# axiom_beta_plugin_module_1xHDMI_v0_6_r1_.net
KiCad netlist of a schematic drawn in EAGLE
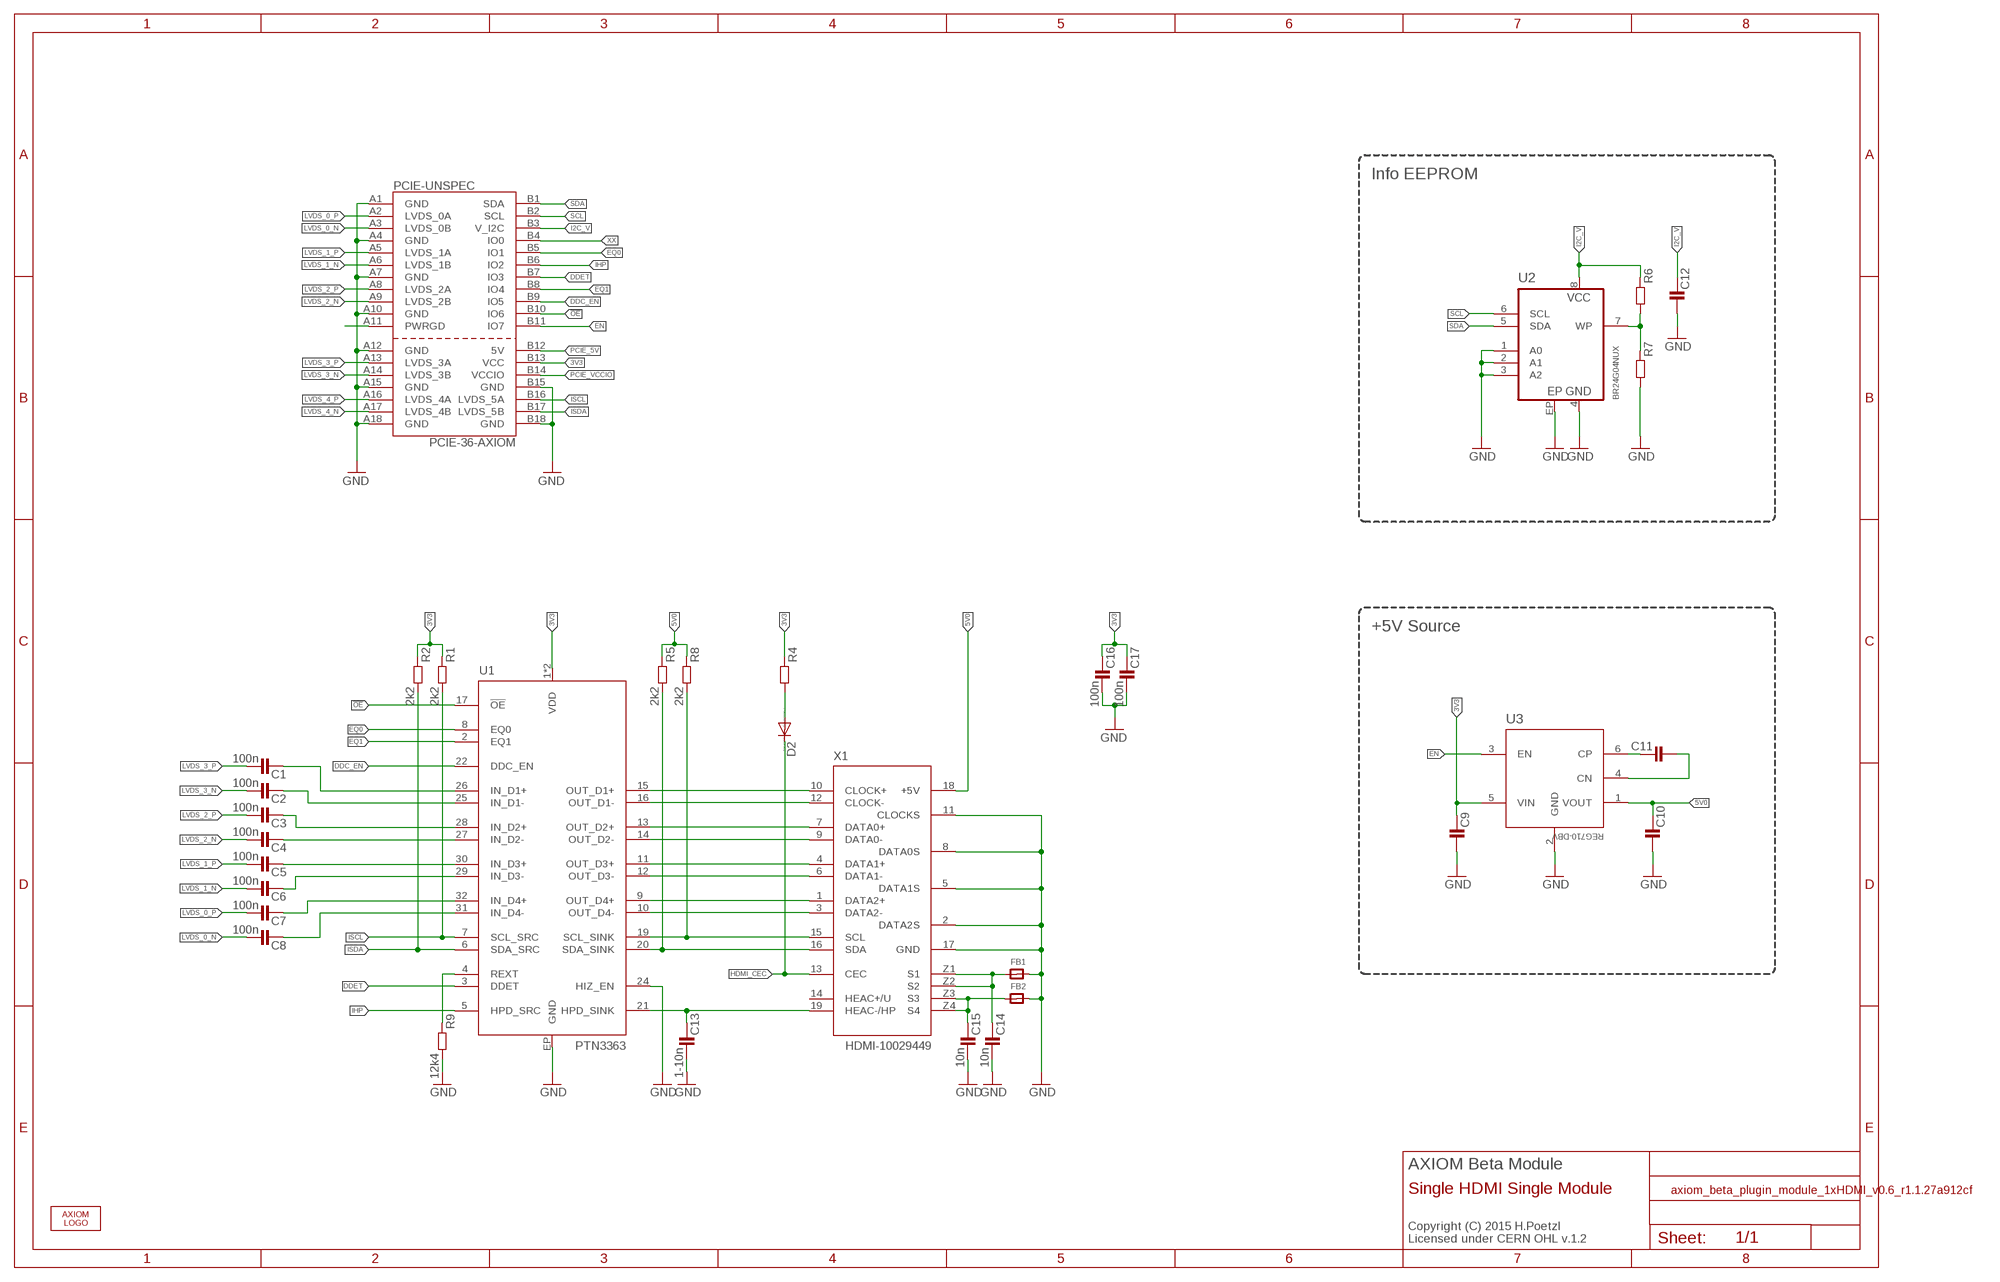
[diagram p0: schematic, sheet 1]

(export (version "E")
  (design (tool "Eeschema 10.0.6"))
  (components
    (comp (ref "C1")
      (value "100n")
      (footprint "eagle-import:0402-C")
      (libsource (lib "eagle-import") (part "C0402-C"))
    )
    (comp (ref "C2")
      (value "100n")
      (footprint "eagle-import:0402-C")
      (libsource (lib "eagle-import") (part "C0402-C"))
    )
    (comp (ref "C3")
      (value "100n")
      (footprint "eagle-import:0402-C")
      (libsource (lib "eagle-import") (part "C0402-C"))
    )
    (comp (ref "C4")
      (value "100n")
      (footprint "eagle-import:0402-C")
      (libsource (lib "eagle-import") (part "C0402-C"))
    )
    (comp (ref "C5")
      (value "100n")
      (footprint "eagle-import:0402-C")
      (libsource (lib "eagle-import") (part "C0402-C"))
    )
    (comp (ref "C6")
      (value "100n")
      (footprint "eagle-import:0402-C")
      (libsource (lib "eagle-import") (part "C0402-C"))
    )
    (comp (ref "C7")
      (value "100n")
      (footprint "eagle-import:0402-C")
      (libsource (lib "eagle-import") (part "C0402-C"))
    )
    (comp (ref "C8")
      (value "100n")
      (footprint "eagle-import:0402-C")
      (libsource (lib "eagle-import") (part "C0402-C"))
    )
    (comp (ref "C9")
      (value "C0603-B")
      (footprint "eagle-import:0603-B")
      (libsource (lib "eagle-import") (part "C0603-B"))
    )
    (comp (ref "C10")
      (value "C0603-B")
      (footprint "eagle-import:0603-B")
      (libsource (lib "eagle-import") (part "C0603-B"))
    )
    (comp (ref "C11")
      (value "C0603-B")
      (footprint "eagle-import:0603-B")
      (libsource (lib "eagle-import") (part "C0603-B"))
    )
    (comp (ref "C12")
      (value "C0402-B")
      (footprint "eagle-import:0402-B")
      (libsource (lib "eagle-import") (part "C0402-B"))
    )
    (comp (ref "C13")
      (value "1-10n")
      (footprint "eagle-import:0402-B")
      (libsource (lib "eagle-import") (part "C0402-B"))
    )
    (comp (ref "C14")
      (value "10n")
      (footprint "eagle-import:0402-B")
      (libsource (lib "eagle-import") (part "C0402-B"))
    )
    (comp (ref "C15")
      (value "10n")
      (footprint "eagle-import:0402-B")
      (libsource (lib "eagle-import") (part "C0402-B"))
    )
    (comp (ref "C16")
      (value "100n")
      (footprint "eagle-import:0402-B")
      (libsource (lib "eagle-import") (part "C0402-B"))
    )
    (comp (ref "C17")
      (value "100n")
      (footprint "eagle-import:0402-B")
      (libsource (lib "eagle-import") (part "C0402-B"))
    )
    (comp (ref "D2")
      (value "DIODE-SOD523")
      (footprint "eagle-import:SOD523")
      (libsource (lib "eagle-import") (part "DIODE-SOD523"))
    )
    (comp (ref "FB1")
      (value "FERRITE_0603MP")
      (footprint "eagle-import:_0603MP")
      (libsource (lib "eagle-import") (part "FERRITE_0603MP"))
    )
    (comp (ref "FB2")
      (value "FERRITE_0603MP")
      (footprint "eagle-import:_0603MP")
      (libsource (lib "eagle-import") (part "FERRITE_0603MP"))
    )
    (comp (ref "PCIE-UNSPEC")
      (value "PCIE-36-AXIOM")
      (footprint "eagle-import:PCIE-36-AXIOM")
      (libsource (lib "eagle-import") (part "PCIE-36-AXIOM"))
    )
    (comp (ref "R1")
      (value "2k2")
      (footprint "eagle-import:0402-B")
      (libsource (lib "eagle-import") (part "R0402-B"))
    )
    (comp (ref "R2")
      (value "2k2")
      (footprint "eagle-import:0402-B")
      (libsource (lib "eagle-import") (part "R0402-B"))
    )
    (comp (ref "R4")
      (value "R0402-B")
      (footprint "eagle-import:0402-B")
      (libsource (lib "eagle-import") (part "R0402-B"))
    )
    (comp (ref "R5")
      (value "2k2")
      (footprint "eagle-import:0402-B")
      (libsource (lib "eagle-import") (part "R0402-B"))
    )
    (comp (ref "R6")
      (value "R0402-B")
      (footprint "eagle-import:0402-B")
      (libsource (lib "eagle-import") (part "R0402-B"))
    )
    (comp (ref "R7")
      (value "R0402-B")
      (footprint "eagle-import:0402-B")
      (libsource (lib "eagle-import") (part "R0402-B"))
    )
    (comp (ref "R8")
      (value "2k2")
      (footprint "eagle-import:0402-B")
      (libsource (lib "eagle-import") (part "R0402-B"))
    )
    (comp (ref "R9")
      (value "12k4")
      (footprint "eagle-import:0402-B")
      (libsource (lib "eagle-import") (part "R0402-B"))
    )
    (comp (ref "U$1")
      (value "AXIOM_LOGO459X70")
      (footprint "eagle-import:AXIOM_LOGO_459X70")
      (libsource (lib "eagle-import") (part "AXIOM_LOGO459X70"))
    )
    (comp (ref "U1")
      (value "PTN3363")
      (footprint "eagle-import:HVQFN32")
      (libsource (lib "eagle-import") (part "PTN3363"))
    )
    (comp (ref "U2")
      (value "BR24G04NUX")
      (footprint "eagle-import:DFN200X300X100-9N")
      (libsource (lib "eagle-import") (part "BR24G04NUX"))
    )
    (comp (ref "U3")
      (value "REG710-DBV")
      (footprint "eagle-import:DBV")
      (libsource (lib "eagle-import") (part "REG710-DBV"))
    )
    (comp (ref "X1")
      (value "HDMI-10029449")
      (footprint "eagle-import:10029449-X01XLF")
      (libsource (lib "eagle-import") (part "HDMI-10029449"))
    )
  )
  (nets
    (net (code "1") (name "/~{OE}") (class "Default")
      (node (ref "PCIE-UNSPEC") (pin "B10") (pinfunction "IO6_B10") (pintype "passive"))
      (node (ref "U1") (pin "17") (pinfunction "~{OE}_17") (pintype "bidirectional"))
    )
    (net (code "2") (name "3V3") (class "Default")
      (node (ref "C16") (pin "1") (pinfunction "1_1") (pintype "passive"))
      (node (ref "C17") (pin "1") (pinfunction "1_1") (pintype "passive"))
      (node (ref "C9") (pin "1") (pinfunction "1_1") (pintype "passive"))
      (node (ref "PCIE-UNSPEC") (pin "B13") (pinfunction "VCC_B13") (pintype "passive"))
      (node (ref "R1") (pin "1") (pinfunction "1_1") (pintype "passive"))
      (node (ref "R2") (pin "1") (pinfunction "1_1") (pintype "passive"))
      (node (ref "R4") (pin "1") (pinfunction "1_1") (pintype "passive"))
      (node (ref "U1") (pin "1") (pinfunction "VDD_1") (pintype "power_in"))
      (node (ref "U1") (pin "18") (pinfunction "VDD_18") (pintype "power_in"))
      (node (ref "U3") (pin "5") (pinfunction "VIN_5") (pintype "power_in"))
    )
    (net (code "3") (name "5V0") (class "Default")
      (node (ref "C10") (pin "1") (pinfunction "1_1") (pintype "passive"))
      (node (ref "R5") (pin "1") (pinfunction "1_1") (pintype "passive"))
      (node (ref "R8") (pin "1") (pinfunction "1_1") (pintype "passive"))
      (node (ref "U3") (pin "1") (pinfunction "VOUT_1") (pintype "output"))
      (node (ref "X1") (pin "18") (pinfunction "+5V_18") (pintype "power_in"))
    )
    (net (code "4") (name "DDC_EN") (class "Default")
      (node (ref "PCIE-UNSPEC") (pin "B9") (pinfunction "IO5_B9") (pintype "passive"))
      (node (ref "U1") (pin "22") (pinfunction "DDC_EN_22") (pintype "bidirectional"))
    )
    (net (code "5") (name "DDET") (class "Default")
      (node (ref "PCIE-UNSPEC") (pin "B7") (pinfunction "IO3_B7") (pintype "passive"))
      (node (ref "U1") (pin "3") (pinfunction "DDET_3") (pintype "bidirectional"))
    )
    (net (code "6") (name "EN") (class "Default")
      (node (ref "PCIE-UNSPEC") (pin "B11") (pinfunction "IO7_B11") (pintype "passive"))
      (node (ref "U3") (pin "3") (pinfunction "EN_3") (pintype "input"))
    )
    (net (code "7") (name "EQ0") (class "Default")
      (node (ref "PCIE-UNSPEC") (pin "B5") (pinfunction "IO1_B5") (pintype "passive"))
      (node (ref "U1") (pin "8") (pinfunction "EQ0_8") (pintype "bidirectional"))
    )
    (net (code "8") (name "EQ1") (class "Default")
      (node (ref "PCIE-UNSPEC") (pin "B8") (pinfunction "IO4_B8") (pintype "passive"))
      (node (ref "U1") (pin "2") (pinfunction "EQ1_2") (pintype "bidirectional"))
    )
    (net (code "9") (name "GND") (class "Default")
      (node (ref "C10") (pin "2") (pinfunction "2_2") (pintype "passive"))
      (node (ref "C12") (pin "2") (pinfunction "2_2") (pintype "passive"))
      (node (ref "C13") (pin "2") (pinfunction "2_2") (pintype "passive"))
      (node (ref "C14") (pin "2") (pinfunction "2_2") (pintype "passive"))
      (node (ref "C15") (pin "2") (pinfunction "2_2") (pintype "passive"))
      (node (ref "C16") (pin "2") (pinfunction "2_2") (pintype "passive"))
      (node (ref "C17") (pin "2") (pinfunction "2_2") (pintype "passive"))
      (node (ref "C9") (pin "2") (pinfunction "2_2") (pintype "passive"))
      (node (ref "FB1") (pin "2") (pinfunction "P$2_2") (pintype "passive"))
      (node (ref "FB2") (pin "2") (pinfunction "P$2_2") (pintype "passive"))
      (node (ref "PCIE-UNSPEC") (pin "A1") (pinfunction "GND_A1") (pintype "passive"))
      (node (ref "PCIE-UNSPEC") (pin "A10") (pinfunction "GND_A10") (pintype "passive"))
      (node (ref "PCIE-UNSPEC") (pin "A12") (pinfunction "GND_A12") (pintype "passive"))
      (node (ref "PCIE-UNSPEC") (pin "A15") (pinfunction "GND_A15") (pintype "passive"))
      (node (ref "PCIE-UNSPEC") (pin "A18") (pinfunction "GND_A18") (pintype "passive"))
      (node (ref "PCIE-UNSPEC") (pin "A4") (pinfunction "GND_A4") (pintype "passive"))
      (node (ref "PCIE-UNSPEC") (pin "A7") (pinfunction "GND_A7") (pintype "passive"))
      (node (ref "PCIE-UNSPEC") (pin "B15") (pinfunction "GND_B15") (pintype "passive"))
      (node (ref "PCIE-UNSPEC") (pin "B18") (pinfunction "GND_B18") (pintype "passive"))
      (node (ref "R7") (pin "2") (pinfunction "2_2") (pintype "passive"))
      (node (ref "R9") (pin "2") (pinfunction "2_2") (pintype "passive"))
      (node (ref "U1") (pin "24") (pinfunction "HIZ_EN_24") (pintype "bidirectional"))
      (node (ref "U1") (pin "EP") (pinfunction "GND_EP") (pintype "bidirectional"))
      (node (ref "U2") (pin "1") (pinfunction "A0_1") (pintype "input"))
      (node (ref "U2") (pin "2") (pinfunction "A1_2") (pintype "input"))
      (node (ref "U2") (pin "3") (pinfunction "A2_3") (pintype "input"))
      (node (ref "U2") (pin "4") (pinfunction "GND_4") (pintype "passive"))
      (node (ref "U2") (pin "EP") (pinfunction "EP_EP") (pintype "passive"))
      (node (ref "U3") (pin "2") (pinfunction "GND_2") (pintype "passive"))
      (node (ref "X1") (pin "11") (pinfunction "CLOCKS_11") (pintype "power_in"))
      (node (ref "X1") (pin "17") (pinfunction "GND_17") (pintype "bidirectional"))
      (node (ref "X1") (pin "2") (pinfunction "DATA2S_2") (pintype "power_in"))
      (node (ref "X1") (pin "5") (pinfunction "DATA1S_5") (pintype "power_in"))
      (node (ref "X1") (pin "8") (pinfunction "DATA0S_8") (pintype "power_in"))
    )
    (net (code "10") (name "HDMI_CEC") (class "Default")
      (node (ref "D2") (pin "C") (pinfunction "C_C") (pintype "passive"))
      (node (ref "X1") (pin "13") (pinfunction "CEC_13") (pintype "bidirectional"))
    )
    (net (code "11") (name "I2C_V") (class "Default")
      (node (ref "C12") (pin "1") (pinfunction "1_1") (pintype "passive"))
      (node (ref "PCIE-UNSPEC") (pin "B3") (pinfunction "V_I2C_B3") (pintype "passive"))
      (node (ref "R6") (pin "1") (pinfunction "1_1") (pintype "passive"))
      (node (ref "U2") (pin "8") (pinfunction "VCC_8") (pintype "power_in"))
    )
    (net (code "12") (name "IHP") (class "Default")
      (node (ref "PCIE-UNSPEC") (pin "B6") (pinfunction "IO2_B6") (pintype "passive"))
      (node (ref "U1") (pin "5") (pinfunction "HPD_SRC_5") (pintype "bidirectional"))
    )
    (net (code "13") (name "ISCL") (class "Default")
      (node (ref "PCIE-UNSPEC") (pin "B16") (pinfunction "LVDS_5A_B16") (pintype "passive"))
      (node (ref "R1") (pin "2") (pinfunction "2_2") (pintype "passive"))
      (node (ref "U1") (pin "7") (pinfunction "SCL_SRC_7") (pintype "bidirectional"))
    )
    (net (code "14") (name "ISDA") (class "Default")
      (node (ref "PCIE-UNSPEC") (pin "B17") (pinfunction "LVDS_5B_B17") (pintype "passive"))
      (node (ref "R2") (pin "2") (pinfunction "2_2") (pintype "passive"))
      (node (ref "U1") (pin "6") (pinfunction "SDA_SRC_6") (pintype "bidirectional"))
    )
    (net (code "15") (name "LVDS_0_N") (class "Default")
      (node (ref "C8") (pin "2") (pinfunction "2_2") (pintype "passive"))
      (node (ref "PCIE-UNSPEC") (pin "A3") (pinfunction "LVDS_0B_A3") (pintype "passive"))
    )
    (net (code "16") (name "LVDS_0_P") (class "Default")
      (node (ref "C7") (pin "2") (pinfunction "2_2") (pintype "passive"))
      (node (ref "PCIE-UNSPEC") (pin "A2") (pinfunction "LVDS_0A_A2") (pintype "passive"))
    )
    (net (code "17") (name "LVDS_1_N") (class "Default")
      (node (ref "C6") (pin "2") (pinfunction "2_2") (pintype "passive"))
      (node (ref "PCIE-UNSPEC") (pin "A6") (pinfunction "LVDS_1B_A6") (pintype "passive"))
    )
    (net (code "18") (name "LVDS_1_P") (class "Default")
      (node (ref "C5") (pin "2") (pinfunction "2_2") (pintype "passive"))
      (node (ref "PCIE-UNSPEC") (pin "A5") (pinfunction "LVDS_1A_A5") (pintype "passive"))
    )
    (net (code "19") (name "LVDS_2_N") (class "Default")
      (node (ref "C4") (pin "2") (pinfunction "2_2") (pintype "passive"))
      (node (ref "PCIE-UNSPEC") (pin "A9") (pinfunction "LVDS_2B_A9") (pintype "passive"))
    )
    (net (code "20") (name "LVDS_2_P") (class "Default")
      (node (ref "C3") (pin "2") (pinfunction "2_2") (pintype "passive"))
      (node (ref "PCIE-UNSPEC") (pin "A8") (pinfunction "LVDS_2A_A8") (pintype "passive"))
    )
    (net (code "21") (name "LVDS_3_N") (class "Default")
      (node (ref "C2") (pin "2") (pinfunction "2_2") (pintype "passive"))
      (node (ref "PCIE-UNSPEC") (pin "A14") (pinfunction "LVDS_3B_A14") (pintype "passive"))
    )
    (net (code "22") (name "LVDS_3_P") (class "Default")
      (node (ref "C1") (pin "2") (pinfunction "2_2") (pintype "passive"))
      (node (ref "PCIE-UNSPEC") (pin "A13") (pinfunction "LVDS_3A_A13") (pintype "passive"))
    )
    (net (code "23") (name "LVDS_4_N") (class "Default")
      (node (ref "PCIE-UNSPEC") (pin "A17") (pinfunction "LVDS_4B_A17") (pintype "passive"))
    )
    (net (code "24") (name "LVDS_4_P") (class "Default")
      (node (ref "PCIE-UNSPEC") (pin "A16") (pinfunction "LVDS_4A_A16") (pintype "passive"))
    )
    (net (code "25") (name "Net-(D2-PadA)") (class "Default")
      (node (ref "D2") (pin "A") (pinfunction "A_A") (pintype "passive"))
      (node (ref "R4") (pin "2") (pinfunction "2_2") (pintype "passive"))
    )
    (net (code "26") (name "Net-(FB1-P$1)") (class "Default")
      (node (ref "C14") (pin "1") (pinfunction "1_1") (pintype "passive"))
      (node (ref "FB1") (pin "1") (pinfunction "P$1_1") (pintype "passive"))
      (node (ref "X1") (pin "Z1") (pinfunction "S1_Z1") (pintype "power_in"))
      (node (ref "X1") (pin "Z2") (pinfunction "S2_Z2") (pintype "power_in"))
    )
    (net (code "27") (name "Net-(FB2-P$1)") (class "Default")
      (node (ref "C15") (pin "1") (pinfunction "1_1") (pintype "passive"))
      (node (ref "FB2") (pin "1") (pinfunction "P$1_1") (pintype "passive"))
      (node (ref "X1") (pin "Z3") (pinfunction "S3_Z3") (pintype "power_in"))
      (node (ref "X1") (pin "Z4") (pinfunction "S4_Z4") (pintype "power_in"))
    )
    (net (code "28") (name "Net-(U1-HPD_SINK)") (class "Default")
      (node (ref "C13") (pin "1") (pinfunction "1_1") (pintype "passive"))
      (node (ref "U1") (pin "21") (pinfunction "HPD_SINK_21") (pintype "bidirectional"))
      (node (ref "X1") (pin "19") (pinfunction "HEAC-/HP_19") (pintype "bidirectional"))
    )
    (net (code "29") (name "Net-(U1-IN_D1+)") (class "Default")
      (node (ref "C1") (pin "1") (pinfunction "1_1") (pintype "passive"))
      (node (ref "U1") (pin "26") (pinfunction "IN_D1+_26") (pintype "bidirectional"))
    )
    (net (code "30") (name "Net-(U1-IN_D1-)") (class "Default")
      (node (ref "C2") (pin "1") (pinfunction "1_1") (pintype "passive"))
      (node (ref "U1") (pin "25") (pinfunction "IN_D1-_25") (pintype "bidirectional"))
    )
    (net (code "31") (name "Net-(U1-IN_D2+)") (class "Default")
      (node (ref "C3") (pin "1") (pinfunction "1_1") (pintype "passive"))
      (node (ref "U1") (pin "28") (pinfunction "IN_D2+_28") (pintype "bidirectional"))
    )
    (net (code "32") (name "Net-(U1-IN_D2-)") (class "Default")
      (node (ref "C4") (pin "1") (pinfunction "1_1") (pintype "passive"))
      (node (ref "U1") (pin "27") (pinfunction "IN_D2-_27") (pintype "bidirectional"))
    )
    (net (code "33") (name "Net-(U1-IN_D3+)") (class "Default")
      (node (ref "C5") (pin "1") (pinfunction "1_1") (pintype "passive"))
      (node (ref "U1") (pin "30") (pinfunction "IN_D3+_30") (pintype "bidirectional"))
    )
    (net (code "34") (name "Net-(U1-IN_D3-)") (class "Default")
      (node (ref "C6") (pin "1") (pinfunction "1_1") (pintype "passive"))
      (node (ref "U1") (pin "29") (pinfunction "IN_D3-_29") (pintype "bidirectional"))
    )
    (net (code "35") (name "Net-(U1-IN_D4+)") (class "Default")
      (node (ref "C7") (pin "1") (pinfunction "1_1") (pintype "passive"))
      (node (ref "U1") (pin "32") (pinfunction "IN_D4+_32") (pintype "bidirectional"))
    )
    (net (code "36") (name "Net-(U1-IN_D4-)") (class "Default")
      (node (ref "C8") (pin "1") (pinfunction "1_1") (pintype "passive"))
      (node (ref "U1") (pin "31") (pinfunction "IN_D4-_31") (pintype "bidirectional"))
    )
    (net (code "37") (name "Net-(U1-OUT_D1+)") (class "Default")
      (node (ref "U1") (pin "15") (pinfunction "OUT_D1+_15") (pintype "bidirectional"))
      (node (ref "X1") (pin "10") (pinfunction "CLOCK+_10") (pintype "bidirectional"))
    )
    (net (code "38") (name "Net-(U1-OUT_D1-)") (class "Default")
      (node (ref "U1") (pin "16") (pinfunction "OUT_D1-_16") (pintype "bidirectional"))
      (node (ref "X1") (pin "12") (pinfunction "CLOCK-_12") (pintype "bidirectional"))
    )
    (net (code "39") (name "Net-(U1-OUT_D2+)") (class "Default")
      (node (ref "U1") (pin "13") (pinfunction "OUT_D2+_13") (pintype "bidirectional"))
      (node (ref "X1") (pin "7") (pinfunction "DATA0+_7") (pintype "bidirectional"))
    )
    (net (code "40") (name "Net-(U1-OUT_D2-)") (class "Default")
      (node (ref "U1") (pin "14") (pinfunction "OUT_D2-_14") (pintype "bidirectional"))
      (node (ref "X1") (pin "9") (pinfunction "DATA0-_9") (pintype "bidirectional"))
    )
    (net (code "41") (name "Net-(U1-OUT_D3+)") (class "Default")
      (node (ref "U1") (pin "11") (pinfunction "OUT_D3+_11") (pintype "bidirectional"))
      (node (ref "X1") (pin "4") (pinfunction "DATA1+_4") (pintype "bidirectional"))
    )
    (net (code "42") (name "Net-(U1-OUT_D3-)") (class "Default")
      (node (ref "U1") (pin "12") (pinfunction "OUT_D3-_12") (pintype "bidirectional"))
      (node (ref "X1") (pin "6") (pinfunction "DATA1-_6") (pintype "bidirectional"))
    )
    (net (code "43") (name "Net-(U1-OUT_D4+)") (class "Default")
      (node (ref "U1") (pin "9") (pinfunction "OUT_D4+_9") (pintype "bidirectional"))
      (node (ref "X1") (pin "1") (pinfunction "DATA2+_1") (pintype "bidirectional"))
    )
    (net (code "44") (name "Net-(U1-OUT_D4-)") (class "Default")
      (node (ref "U1") (pin "10") (pinfunction "OUT_D4-_10") (pintype "bidirectional"))
      (node (ref "X1") (pin "3") (pinfunction "DATA2-_3") (pintype "bidirectional"))
    )
    (net (code "45") (name "Net-(U1-REXT)") (class "Default")
      (node (ref "R9") (pin "1") (pinfunction "1_1") (pintype "passive"))
      (node (ref "U1") (pin "4") (pinfunction "REXT_4") (pintype "bidirectional"))
    )
    (net (code "46") (name "Net-(U1-SCL_SINK)") (class "Default")
      (node (ref "R8") (pin "2") (pinfunction "2_2") (pintype "passive"))
      (node (ref "U1") (pin "19") (pinfunction "SCL_SINK_19") (pintype "bidirectional"))
      (node (ref "X1") (pin "15") (pinfunction "SCL_15") (pintype "bidirectional"))
    )
    (net (code "47") (name "Net-(U1-SDA_SINK)") (class "Default")
      (node (ref "R5") (pin "2") (pinfunction "2_2") (pintype "passive"))
      (node (ref "U1") (pin "20") (pinfunction "SDA_SINK_20") (pintype "bidirectional"))
      (node (ref "X1") (pin "16") (pinfunction "SDA_16") (pintype "bidirectional"))
    )
    (net (code "48") (name "Net-(U2-WP)") (class "Default")
      (node (ref "R6") (pin "2") (pinfunction "2_2") (pintype "passive"))
      (node (ref "R7") (pin "1") (pinfunction "1_1") (pintype "passive"))
      (node (ref "U2") (pin "7") (pinfunction "WP_7") (pintype "input"))
    )
    (net (code "49") (name "Net-(U3-CN)") (class "Default")
      (node (ref "C11") (pin "2") (pinfunction "2_2") (pintype "passive"))
      (node (ref "U3") (pin "4") (pinfunction "CN_4") (pintype "power_in"))
    )
    (net (code "50") (name "Net-(U3-CP)") (class "Default")
      (node (ref "C11") (pin "1") (pinfunction "1_1") (pintype "passive"))
      (node (ref "U3") (pin "6") (pinfunction "CP_6") (pintype "output"))
    )
    (net (code "51") (name "PCIE_5V") (class "Default")
      (node (ref "PCIE-UNSPEC") (pin "B12") (pinfunction "5V_B12") (pintype "passive"))
    )
    (net (code "52") (name "PCIE_VCCIO") (class "Default")
      (node (ref "PCIE-UNSPEC") (pin "B14") (pinfunction "VCCIO_B14") (pintype "passive"))
    )
    (net (code "53") (name "SCL") (class "Default")
      (node (ref "PCIE-UNSPEC") (pin "B2") (pinfunction "SCL_B2") (pintype "passive"))
      (node (ref "U2") (pin "6") (pinfunction "SCL_6") (pintype "input"))
    )
    (net (code "54") (name "SDA") (class "Default")
      (node (ref "PCIE-UNSPEC") (pin "B1") (pinfunction "SDA_B1") (pintype "passive"))
      (node (ref "U2") (pin "5") (pinfunction "SDA_5") (pintype "bidirectional"))
    )
    (net (code "55") (name "XX") (class "Default")
      (node (ref "PCIE-UNSPEC") (pin "B4") (pinfunction "IO0_B4") (pintype "passive"))
    )
    (net (code "56") (name "unconnected-(PCIE-UNSPEC-PWRGD-PadA11)") (class "Default")
      (node (ref "PCIE-UNSPEC") (pin "A11") (pinfunction "PWRGD_A11") (pintype "passive"))
    )
    (net (code "57") (name "unconnected-(X1-HEAC+{slash}U-Pad14)") (class "Default")
      (node (ref "X1") (pin "14") (pinfunction "HEAC+/U_14") (pintype "bidirectional"))
    )
  )
)
